# Power.net
KiCad netlist of a schematic drawn in Altium Designer
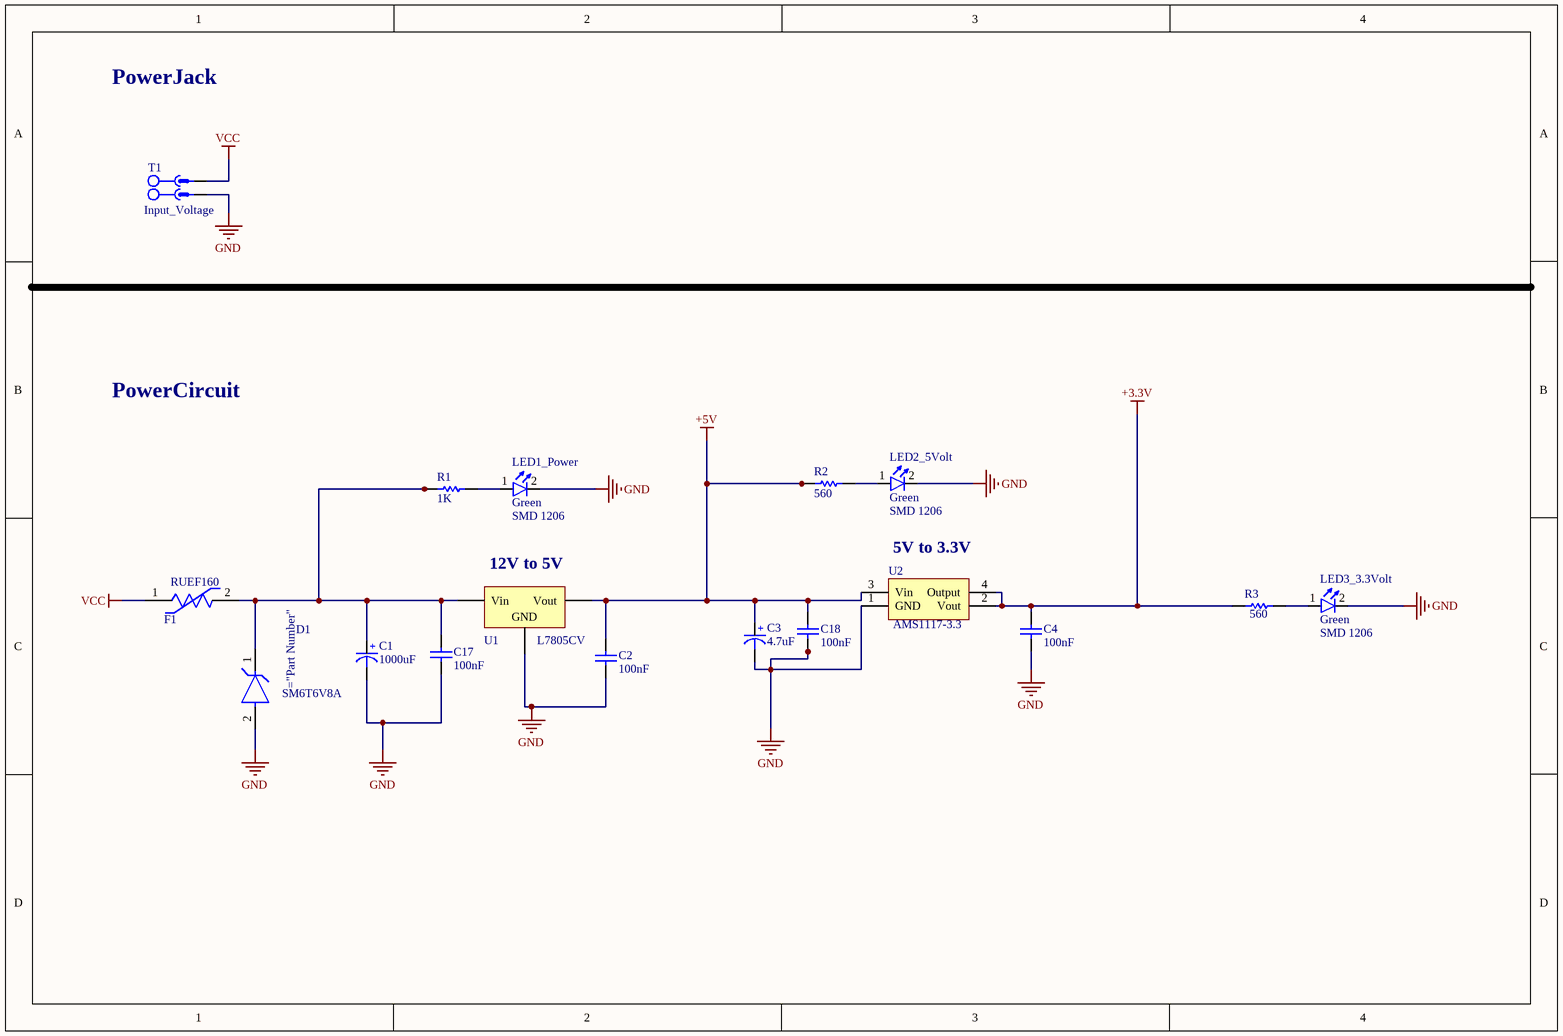
[diagram p0: Power.SchDoc]

(export (version "E")
  (design (tool "Eeschema 10.0.6"))
  (components
    (comp (ref "C1")
      (value "1000uF")
      (footprint "cap 01")
      (description "Polar Capacitor")
      (fields
        (field (name "VOLTAGE") "16V")
        (field (name "DESIGNER") "Eng. Saeid Jorablo")
        (field (name "PUBLISHER") "SJ Unlimited")
      )
      (libsource (lib "Passive Components") (part "CAP_Polar"))
    )
    (comp (ref "C2")
      (value "100nF")
      (footprint "CAPC3216L (1206)")
      (description "Bipolar Capacitor")
      (fields
        (field (name "VOLTAGE") "100V")
        (field (name "DESIGNER") "Eng. Saeid Jorablo")
        (field (name "PUBLISHER") "SJ Unlimited")
      )
      (libsource (lib "Passive Components") (part "CAP_Bipolar"))
    )
    (comp (ref "C3")
      (value "4.7uF")
      (footprint "cap 01")
      (description "Polar Capacitor")
      (fields
        (field (name "VOLTAGE") "16V")
        (field (name "DESIGNER") "Eng. Saeid Jorablo")
        (field (name "PUBLISHER") "SJ Unlimited")
      )
      (libsource (lib "Passive Components") (part "CAP_Polar"))
    )
    (comp (ref "C4")
      (value "100nF")
      (footprint "CAPC3216L (1206)")
      (description "Bipolar Capacitor")
      (fields
        (field (name "VOLTAGE") "100V")
        (field (name "DESIGNER") "Eng. Saeid Jorablo")
        (field (name "PUBLISHER") "SJ Unlimited")
      )
      (libsource (lib "Passive Components") (part "CAP_Bipolar"))
    )
    (comp (ref "C17")
      (value "100nF")
      (footprint "CAPC3216L (1206)")
      (description "Bipolar Capacitor")
      (fields
        (field (name "VOLTAGE") "100V")
        (field (name "DESIGNER") "Eng. Saeid Jorablo")
        (field (name "PUBLISHER") "SJ Unlimited")
      )
      (libsource (lib "Passive Components") (part "CAP_Bipolar"))
    )
    (comp (ref "C18")
      (value "100nF")
      (footprint "CAPC3216L (1206)")
      (description "Bipolar Capacitor")
      (fields
        (field (name "VOLTAGE") "100V")
        (field (name "DESIGNER") "Eng. Saeid Jorablo")
        (field (name "PUBLISHER") "SJ Unlimited")
      )
      (libsource (lib "Passive Components") (part "CAP_Bipolar"))
    )
    (comp (ref "D1")
      (value "SM6T6V8A")
      (footprint "STMicroelectronics_SM6T6V8A_0")
      (description "TVS DIODE 5.8VWM 13.4VC SMB")
      (libsource (lib "Amir_Lib") (part "SM6T6V8A"))
    )
    (comp (ref "F1")
      (value "RUEF160")
      (footprint "Littelfuse_RUEF160")
      (libsource (lib "Amir_Lib") (part "RUEF160"))
    )
    (comp (ref "LED1_Power")
      (value "Green")
      (footprint "LED SMD 1206")
      (fields
        (field (name "COLOR") "Green")
        (field (name "SIZE") "SMD 1206")
        (field (name "DESIGNER") "Saeid Jorablo")
      )
      (libsource (lib "My_Library") (part "LED"))
    )
    (comp (ref "LED2_5Volt")
      (value "Green")
      (footprint "LED SMD 1206")
      (fields
        (field (name "COLOR") "Green")
        (field (name "SIZE") "SMD 1206")
        (field (name "DESIGNER") "Saeid Jorablo")
      )
      (libsource (lib "My_Library") (part "LED"))
    )
    (comp (ref "LED3_3.3Volt")
      (value "Green")
      (footprint "LED SMD 1206")
      (fields
        (field (name "COLOR") "Green")
        (field (name "SIZE") "SMD 1206")
        (field (name "DESIGNER") "Saeid Jorablo")
      )
      (libsource (lib "My_Library") (part "LED"))
    )
    (comp (ref "R1")
      (value "1K")
      (footprint "RESC4817X04N")
      (description "RES 1206")
      (fields (field (name "DESIGNER") "Abbas Basereh"))
      (libsource (lib "General 1") (part "RES 1206 0.25W"))
    )
    (comp (ref "R2")
      (value "560")
      (footprint "RESC4817X04N")
      (description "RES 1206")
      (fields (field (name "DESIGNER") "Abbas Basereh"))
      (libsource (lib "General 1") (part "RES 1206 0.25W"))
    )
    (comp (ref "R3")
      (value "560")
      (footprint "RESC4817X04N")
      (description "RES 1206")
      (fields (field (name "DESIGNER") "Abbas Basereh"))
      (libsource (lib "General 1") (part "RES 1206 0.25W"))
    )
    (comp (ref "T1")
      (value "Input_Voltage")
      (footprint "MSTBV 2,5/2-G-5")
      (description "2 Pitch: 5 mm Color: green Contact surface: Tin Assembly")
      (fields
        (field (name "MANUFACTURER") "PHOENIX CONTACT")
        (field (name "VOLTAGE") "320 V")
        (field (name "DESIGNER") "ABBAS BASEREH")
      )
      (libsource (lib "General 1") (part "CON_Phoenix_MSTBV_02"))
    )
    (comp (ref "U1")
      (value "L7805CV")
      (footprint "TO-220 AB")
      (description "Linear Voltage Regulator IC Positive FIXED")
      (fields (field (name "MANUFACTURER") "STMicroelectronics") (field (name "DESIGNER") "Abbas Basereh"))
      (libsource (lib "General 1") (part "L7805CV-Linear Voltage Regulator IC Positive 1 Output 5V 1.5A TO-220AB"))
    )
    (comp (ref "U2")
      (value "AMS1117-3.3")
      (footprint "SOT223-4N")
      (description "800mA LOW DROPOUT VOLTAGE REGULATOR")
      (fields
        (field (name "MANUFACTURER") "Advanced Monolithic Systems, Inc.")
        (field (name "DESIGNER") "Eng. Saeid Jorablo")
      )
      (libsource (lib "General 3") (part "IC_AMS1117-3.3"))
    )
  )
  (nets
    (net (code "1") (name "+3.3V") (class "Default")
      (node (ref "C4") (pin "1") (pinfunction "+_1") (pintype "passive"))
      (node (ref "R3") (pin "1") (pinfunction "1_1") (pintype "passive"))
      (node (ref "U2") (pin "2") (pinfunction "Vout_2") (pintype "passive"))
      (node (ref "U2") (pin "4") (pinfunction "Output_4") (pintype "passive"))
    )
    (net (code "2") (name "+5V") (class "Default")
      (node (ref "C18") (pin "1") (pinfunction "+_1") (pintype "passive"))
      (node (ref "C2") (pin "1") (pinfunction "+_1") (pintype "passive"))
      (node (ref "C3") (pin "1") (pinfunction "+_1") (pintype "passive"))
      (node (ref "R2") (pin "1") (pinfunction "1_1") (pintype "passive"))
      (node (ref "U1") (pin "3") (pinfunction "Vout_3") (pintype "passive"))
      (node (ref "U2") (pin "3") (pinfunction "Vin_3") (pintype "passive"))
    )
    (net (code "3") (name "GND") (class "Default")
      (node (ref "C1") (pin "2") (pinfunction "-_2") (pintype "passive"))
      (node (ref "C17") (pin "2") (pinfunction "-_2") (pintype "passive"))
      (node (ref "C18") (pin "2") (pinfunction "-_2") (pintype "passive"))
      (node (ref "C2") (pin "2") (pinfunction "-_2") (pintype "passive"))
      (node (ref "C3") (pin "2") (pinfunction "-_2") (pintype "passive"))
      (node (ref "C4") (pin "2") (pinfunction "-_2") (pintype "passive"))
      (node (ref "D1") (pin "2") (pinfunction "A_2") (pintype "passive"))
      (node (ref "LED1_Power") (pin "2") (pinfunction "K_2") (pintype "passive"))
      (node (ref "LED2_5Volt") (pin "2") (pinfunction "K_2") (pintype "passive"))
      (node (ref "LED3_3.3Volt") (pin "2") (pinfunction "K_2") (pintype "passive"))
      (node (ref "T1") (pin "1") (pinfunction "1_1") (pintype "passive"))
      (node (ref "U1") (pin "2") (pinfunction "GND_2") (pintype "passive"))
      (node (ref "U2") (pin "1") (pinfunction "GND_1") (pintype "passive"))
    )
    (net (code "4") (name "Net-(C1-+)") (class "Default")
      (node (ref "C1") (pin "1") (pinfunction "+_1") (pintype "passive"))
      (node (ref "C17") (pin "1") (pinfunction "+_1") (pintype "passive"))
      (node (ref "D1") (pin "1") (pinfunction "K_1") (pintype "passive"))
      (node (ref "F1") (pin "2") (pinfunction "2_2") (pintype "passive"))
      (node (ref "R1") (pin "1") (pinfunction "1_1") (pintype "passive"))
      (node (ref "U1") (pin "1") (pinfunction "Vin_1") (pintype "passive"))
    )
    (net (code "5") (name "Net-(LED1_Power-A)") (class "Default")
      (node (ref "LED1_Power") (pin "1") (pinfunction "A_1") (pintype "passive"))
      (node (ref "R1") (pin "2") (pinfunction "2_2") (pintype "passive"))
    )
    (net (code "6") (name "Net-(LED2_5Volt-A)") (class "Default")
      (node (ref "LED2_5Volt") (pin "1") (pinfunction "A_1") (pintype "passive"))
      (node (ref "R2") (pin "2") (pinfunction "2_2") (pintype "passive"))
    )
    (net (code "7") (name "Net-(LED3_3.3Volt-A)") (class "Default")
      (node (ref "LED3_3.3Volt") (pin "1") (pinfunction "A_1") (pintype "passive"))
      (node (ref "R3") (pin "2") (pinfunction "2_2") (pintype "passive"))
    )
    (net (code "8") (name "VCC") (class "Default")
      (node (ref "F1") (pin "1") (pinfunction "1_1") (pintype "passive"))
      (node (ref "T1") (pin "2") (pinfunction "2_2") (pintype "passive"))
    )
  )
)
